# buck_converter.net
KiCad netlist of a schematic drawn in EAGLE
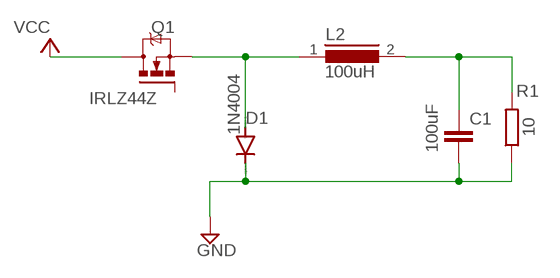
[diagram p0: schematic, sheet 1]

(export (version "E")
  (design (tool "Eeschema 10.0.6"))
  (components
    (comp (ref "C1")
      (value "100uF")
      (footprint "eagle-import:C7.5B3")
      (libsource (lib "eagle-import") (part "C7.5/3"))
    )
    (comp (ref "D1")
      (value "1N4004")
      (footprint "eagle-import:DO41-10")
      (libsource (lib "eagle-import") (part "1N4004"))
    )
    (comp (ref "L2")
      (value "100uH")
      (footprint "eagle-import:82114R")
      (libsource (lib "eagle-import") (part "82114R"))
    )
    (comp (ref "Q1")
      (value "IRLZ44Z")
      (footprint "eagle-import:TO220BH")
      (libsource (lib "eagle-import") (part "IRLZ44Z"))
    )
    (comp (ref "R1")
      (value "10")
      (footprint "eagle-import:R0805")
      (libsource (lib "eagle-import") (part "R-EU_R0805"))
    )
  )
  (nets
    (net (code "1") (name "GND") (class "Default")
      (node (ref "C1") (pin "2") (pinfunction "2_2") (pintype "passive"))
      (node (ref "D1") (pin "C") (pinfunction "C_C") (pintype "passive"))
      (node (ref "R1") (pin "1") (pinfunction "1_1") (pintype "passive"))
    )
    (net (code "2") (name "Net-(C1-Pad1)") (class "Default")
      (node (ref "C1") (pin "1") (pinfunction "1_1") (pintype "passive"))
      (node (ref "L2") (pin "2") (pinfunction "2_2") (pintype "passive"))
      (node (ref "R1") (pin "2") (pinfunction "2_2") (pintype "passive"))
    )
    (net (code "3") (name "Net-(D1-PadA)") (class "Default")
      (node (ref "D1") (pin "A") (pinfunction "A_A") (pintype "passive"))
      (node (ref "L2") (pin "1") (pinfunction "1_1") (pintype "passive"))
      (node (ref "Q1") (pin "S") (pinfunction "S_S") (pintype "passive"))
    )
    (net (code "4") (name "VCC") (class "Default")
      (node (ref "Q1") (pin "D") (pinfunction "D_D") (pintype "passive"))
    )
    (net (code "5") (name "unconnected-(Q1-PadG)") (class "Default")
      (node (ref "Q1") (pin "G") (pinfunction "G_G") (pintype "passive"))
    )
  )
)
